# Power.net
KiCad netlist of a schematic drawn in Altium Designer
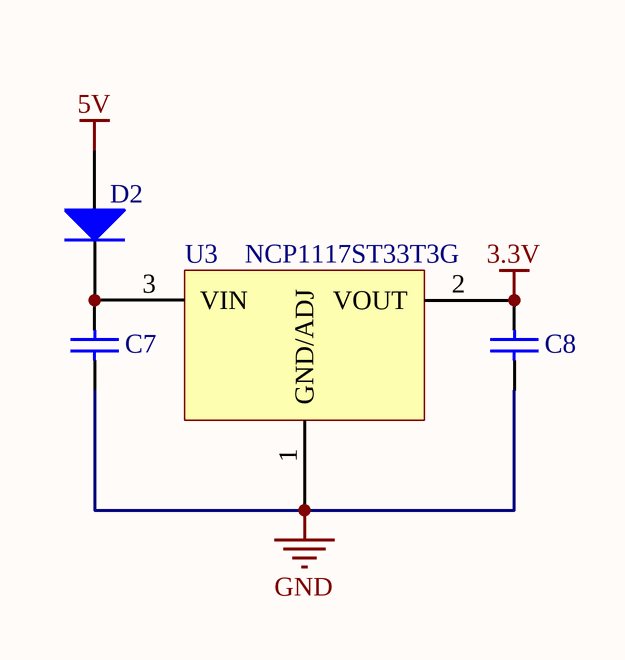
[diagram p0: Power.SchDoc]

(export (version "E")
  (design (tool "Eeschema 10.0.6"))
  (components
    (comp (ref "C7")
      (value "10uF")
      (footprint "CAP-0603")
      (description "贴片电容")
      (libsource (lib "Power_Lib_Altium") (part "CAP"))
    )
    (comp (ref "C8")
      (value "10uF")
      (footprint "CAP-0603")
      (description "贴片电容")
      (libsource (lib "Power_Lib_Altium") (part "CAP"))
    )
    (comp (ref "D2")
      (value "SS14 6V")
      (footprint "SOD_123")
      (description "二极管")
      (libsource (lib "Power_Lib_Altium") (part "DIODE"))
    )
    (comp (ref "U3")
      (value "NCP1117ST33T3G")
      (footprint "SOT-223")
      (description "NCP1117, NCV1117. 1.0 A Low-Dropout Positive  Fixed and Adjustable  Voltage Regulators")
      (libsource (lib "Power_Lib_Altium") (part "NCP1117"))
    )
  )
  (nets
    (net (code "1") (name "3.3V") (class "Default")
      (node (ref "C8") (pin "2") (pinfunction "2_2") (pintype "passive"))
      (node (ref "U3") (pin "2") (pinfunction "VOUT_2") (pintype "passive"))
    )
    (net (code "2") (name "5V") (class "Default")
      (node (ref "D2") (pin "1") (pinfunction "A_1") (pintype "passive"))
    )
    (net (code "3") (name "GND") (class "Default")
      (node (ref "C7") (pin "1") (pinfunction "1_1") (pintype "passive"))
      (node (ref "C8") (pin "1") (pinfunction "1_1") (pintype "passive"))
      (node (ref "U3") (pin "1") (pinfunction "GND/ADJ_1") (pintype "passive"))
    )
    (net (code "4") (name "Net-(D2-K)") (class "Default")
      (node (ref "C7") (pin "2") (pinfunction "2_2") (pintype "passive"))
      (node (ref "D2") (pin "2") (pinfunction "K_2") (pintype "passive"))
      (node (ref "U3") (pin "3") (pinfunction "VIN_3") (pintype "passive"))
    )
  )
)
